# 4x4-programmable-keypad.net
KiCad netlist of a schematic drawn in EAGLE
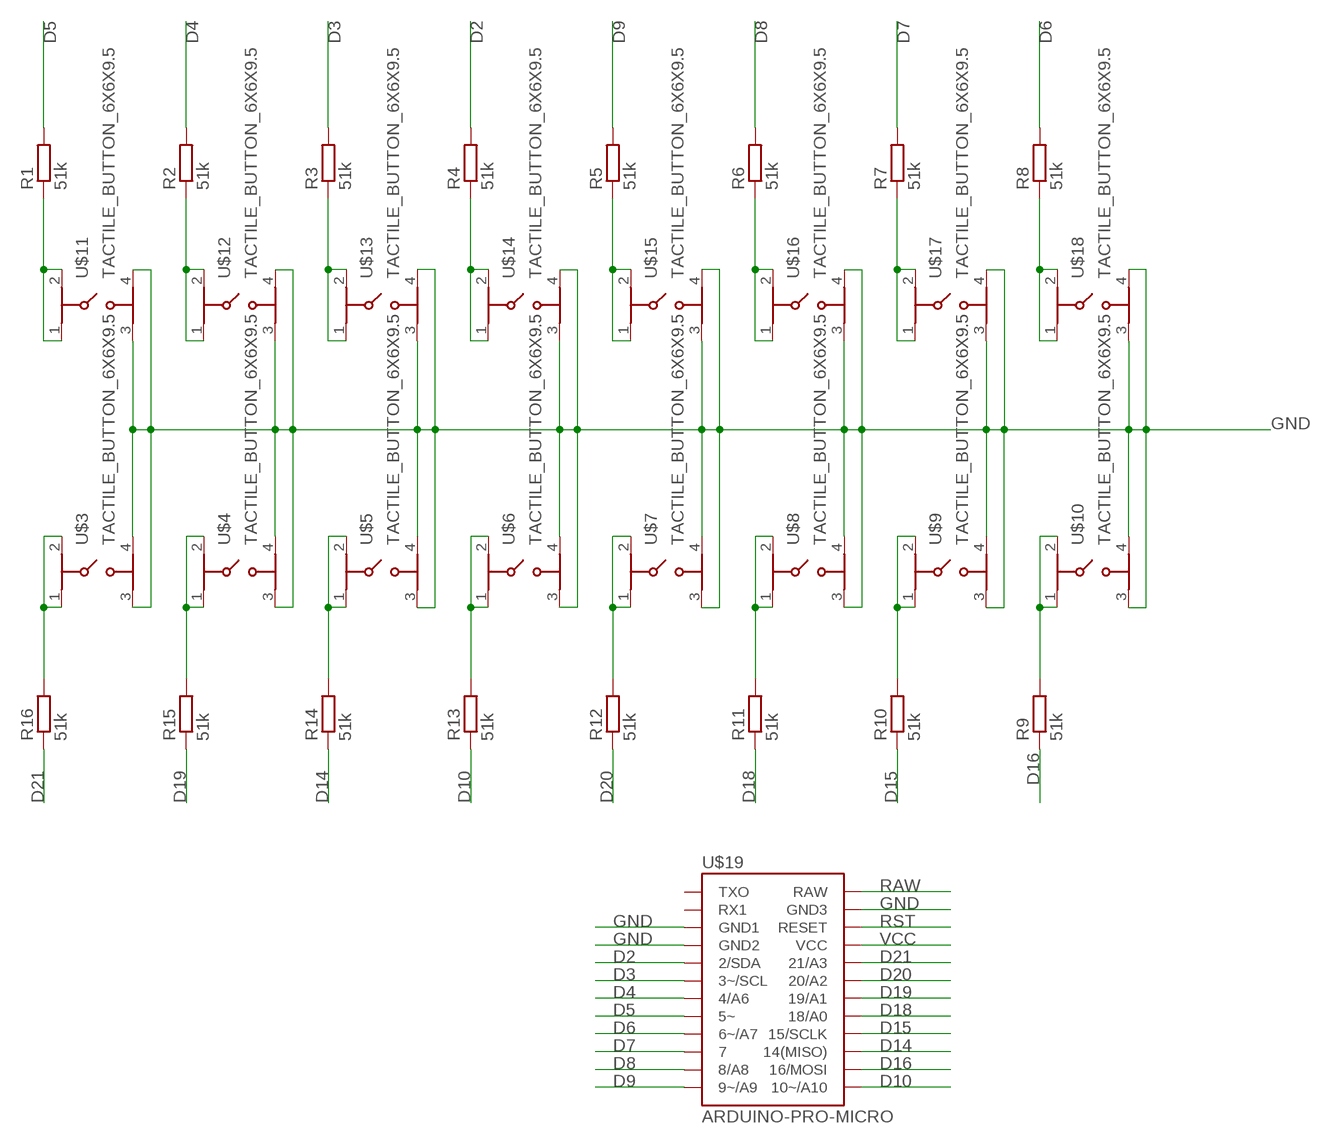
[diagram p0: schematic, sheet 1]

(export (version "E")
  (design (tool "Eeschema 10.0.6"))
  (components
    (comp (ref "R1")
      (value "51k")
      (footprint "eagle-import:R0603")
      (libsource (lib "eagle-import") (part "R-EU_R0603"))
    )
    (comp (ref "R2")
      (value "51k")
      (footprint "eagle-import:R0603")
      (libsource (lib "eagle-import") (part "R-EU_R0603"))
    )
    (comp (ref "R3")
      (value "51k")
      (footprint "eagle-import:R0603")
      (libsource (lib "eagle-import") (part "R-EU_R0603"))
    )
    (comp (ref "R4")
      (value "51k")
      (footprint "eagle-import:R0603")
      (libsource (lib "eagle-import") (part "R-EU_R0603"))
    )
    (comp (ref "R5")
      (value "51k")
      (footprint "eagle-import:R0603")
      (libsource (lib "eagle-import") (part "R-EU_R0603"))
    )
    (comp (ref "R6")
      (value "51k")
      (footprint "eagle-import:R0603")
      (libsource (lib "eagle-import") (part "R-EU_R0603"))
    )
    (comp (ref "R7")
      (value "51k")
      (footprint "eagle-import:R0603")
      (libsource (lib "eagle-import") (part "R-EU_R0603"))
    )
    (comp (ref "R8")
      (value "51k")
      (footprint "eagle-import:R0603")
      (libsource (lib "eagle-import") (part "R-EU_R0603"))
    )
    (comp (ref "R9")
      (value "51k")
      (footprint "eagle-import:R0603")
      (libsource (lib "eagle-import") (part "R-EU_R0603"))
    )
    (comp (ref "R10")
      (value "51k")
      (footprint "eagle-import:R0603")
      (libsource (lib "eagle-import") (part "R-EU_R0603"))
    )
    (comp (ref "R11")
      (value "51k")
      (footprint "eagle-import:R0603")
      (libsource (lib "eagle-import") (part "R-EU_R0603"))
    )
    (comp (ref "R12")
      (value "51k")
      (footprint "eagle-import:R0603")
      (libsource (lib "eagle-import") (part "R-EU_R0603"))
    )
    (comp (ref "R13")
      (value "51k")
      (footprint "eagle-import:R0603")
      (libsource (lib "eagle-import") (part "R-EU_R0603"))
    )
    (comp (ref "R14")
      (value "51k")
      (footprint "eagle-import:R0603")
      (libsource (lib "eagle-import") (part "R-EU_R0603"))
    )
    (comp (ref "R15")
      (value "51k")
      (footprint "eagle-import:R0603")
      (libsource (lib "eagle-import") (part "R-EU_R0603"))
    )
    (comp (ref "R16")
      (value "51k")
      (footprint "eagle-import:R0603")
      (libsource (lib "eagle-import") (part "R-EU_R0603"))
    )
    (comp (ref "U$3")
      (value "TACTILE_BUTTON_6X6X9.5")
      (footprint "eagle-import:TACTILE_SWITCH_PTH_6.0MM")
      (libsource (lib "eagle-import") (part "TACTILE_BUTTON_6X6X9.5"))
    )
    (comp (ref "U$4")
      (value "TACTILE_BUTTON_6X6X9.5")
      (footprint "eagle-import:TACTILE_SWITCH_PTH_6.0MM")
      (libsource (lib "eagle-import") (part "TACTILE_BUTTON_6X6X9.5"))
    )
    (comp (ref "U$5")
      (value "TACTILE_BUTTON_6X6X9.5")
      (footprint "eagle-import:TACTILE_SWITCH_PTH_6.0MM")
      (libsource (lib "eagle-import") (part "TACTILE_BUTTON_6X6X9.5"))
    )
    (comp (ref "U$6")
      (value "TACTILE_BUTTON_6X6X9.5")
      (footprint "eagle-import:TACTILE_SWITCH_PTH_6.0MM")
      (libsource (lib "eagle-import") (part "TACTILE_BUTTON_6X6X9.5"))
    )
    (comp (ref "U$7")
      (value "TACTILE_BUTTON_6X6X9.5")
      (footprint "eagle-import:TACTILE_SWITCH_PTH_6.0MM")
      (libsource (lib "eagle-import") (part "TACTILE_BUTTON_6X6X9.5"))
    )
    (comp (ref "U$8")
      (value "TACTILE_BUTTON_6X6X9.5")
      (footprint "eagle-import:TACTILE_SWITCH_PTH_6.0MM")
      (libsource (lib "eagle-import") (part "TACTILE_BUTTON_6X6X9.5"))
    )
    (comp (ref "U$9")
      (value "TACTILE_BUTTON_6X6X9.5")
      (footprint "eagle-import:TACTILE_SWITCH_PTH_6.0MM")
      (libsource (lib "eagle-import") (part "TACTILE_BUTTON_6X6X9.5"))
    )
    (comp (ref "U$10")
      (value "TACTILE_BUTTON_6X6X9.5")
      (footprint "eagle-import:TACTILE_SWITCH_PTH_6.0MM")
      (libsource (lib "eagle-import") (part "TACTILE_BUTTON_6X6X9.5"))
    )
    (comp (ref "U$11")
      (value "TACTILE_BUTTON_6X6X9.5")
      (footprint "eagle-import:TACTILE_SWITCH_PTH_6.0MM")
      (libsource (lib "eagle-import") (part "TACTILE_BUTTON_6X6X9.5"))
    )
    (comp (ref "U$12")
      (value "TACTILE_BUTTON_6X6X9.5")
      (footprint "eagle-import:TACTILE_SWITCH_PTH_6.0MM")
      (libsource (lib "eagle-import") (part "TACTILE_BUTTON_6X6X9.5"))
    )
    (comp (ref "U$13")
      (value "TACTILE_BUTTON_6X6X9.5")
      (footprint "eagle-import:TACTILE_SWITCH_PTH_6.0MM")
      (libsource (lib "eagle-import") (part "TACTILE_BUTTON_6X6X9.5"))
    )
    (comp (ref "U$14")
      (value "TACTILE_BUTTON_6X6X9.5")
      (footprint "eagle-import:TACTILE_SWITCH_PTH_6.0MM")
      (libsource (lib "eagle-import") (part "TACTILE_BUTTON_6X6X9.5"))
    )
    (comp (ref "U$15")
      (value "TACTILE_BUTTON_6X6X9.5")
      (footprint "eagle-import:TACTILE_SWITCH_PTH_6.0MM")
      (libsource (lib "eagle-import") (part "TACTILE_BUTTON_6X6X9.5"))
    )
    (comp (ref "U$16")
      (value "TACTILE_BUTTON_6X6X9.5")
      (footprint "eagle-import:TACTILE_SWITCH_PTH_6.0MM")
      (libsource (lib "eagle-import") (part "TACTILE_BUTTON_6X6X9.5"))
    )
    (comp (ref "U$17")
      (value "TACTILE_BUTTON_6X6X9.5")
      (footprint "eagle-import:TACTILE_SWITCH_PTH_6.0MM")
      (libsource (lib "eagle-import") (part "TACTILE_BUTTON_6X6X9.5"))
    )
    (comp (ref "U$18")
      (value "TACTILE_BUTTON_6X6X9.5")
      (footprint "eagle-import:TACTILE_SWITCH_PTH_6.0MM")
      (libsource (lib "eagle-import") (part "TACTILE_BUTTON_6X6X9.5"))
    )
    (comp (ref "U$19")
      (value "ARDUINO-PRO-MICRO")
      (footprint "eagle-import:SPARKFUN_PRO_MICRO")
      (libsource (lib "eagle-import") (part "ARDUINO-PRO-MICRO"))
    )
  )
  (nets
    (net (code "1") (name "/D2") (class "Default")
      (node (ref "R4") (pin "2") (pinfunction "2_2") (pintype "passive"))
      (node (ref "U$19") (pin "2/SDA") (pinfunction "2/SDA_2/SDA") (pintype "bidirectional"))
    )
    (net (code "2") (name "/D3") (class "Default")
      (node (ref "R3") (pin "2") (pinfunction "2_2") (pintype "passive"))
      (node (ref "U$19") (pin "3~/SCL") (pinfunction "3~{/SCL}_3~/SCL") (pintype "bidirectional"))
    )
    (net (code "3") (name "/D4") (class "Default")
      (node (ref "R2") (pin "2") (pinfunction "2_2") (pintype "passive"))
      (node (ref "U$19") (pin "4/A6") (pinfunction "4/A6_4/A6") (pintype "bidirectional"))
    )
    (net (code "4") (name "/D5") (class "Default")
      (node (ref "R1") (pin "2") (pinfunction "2_2") (pintype "passive"))
      (node (ref "U$19") (pin "5~") (pinfunction "5~{}_5~") (pintype "bidirectional"))
    )
    (net (code "5") (name "/D6") (class "Default")
      (node (ref "R8") (pin "2") (pinfunction "2_2") (pintype "passive"))
      (node (ref "U$19") (pin "6~/A7") (pinfunction "6~{/A7}_6~/A7") (pintype "bidirectional"))
    )
    (net (code "6") (name "/D7") (class "Default")
      (node (ref "R7") (pin "2") (pinfunction "2_2") (pintype "passive"))
      (node (ref "U$19") (pin "7") (pinfunction "7_7") (pintype "bidirectional"))
    )
    (net (code "7") (name "/D8") (class "Default")
      (node (ref "R6") (pin "2") (pinfunction "2_2") (pintype "passive"))
      (node (ref "U$19") (pin "8/A8") (pinfunction "8/A8_8/A8") (pintype "bidirectional"))
    )
    (net (code "8") (name "/D9") (class "Default")
      (node (ref "R5") (pin "2") (pinfunction "2_2") (pintype "passive"))
      (node (ref "U$19") (pin "9~/A9") (pinfunction "9~{/A9}_9~/A9") (pintype "bidirectional"))
    )
    (net (code "9") (name "/D10") (class "Default")
      (node (ref "R13") (pin "1") (pinfunction "1_1") (pintype "passive"))
      (node (ref "U$19") (pin "10~/A10") (pinfunction "10~{/A10}_10~/A10") (pintype "bidirectional"))
    )
    (net (code "10") (name "/D14") (class "Default")
      (node (ref "R14") (pin "1") (pinfunction "1_1") (pintype "passive"))
      (node (ref "U$19") (pin "14/MISO") (pinfunction "14(MISO)_14/MISO") (pintype "bidirectional"))
    )
    (net (code "11") (name "/D15") (class "Default")
      (node (ref "R10") (pin "1") (pinfunction "1_1") (pintype "passive"))
      (node (ref "U$19") (pin "15/SCLK") (pinfunction "15/SCLK_15/SCLK") (pintype "bidirectional"))
    )
    (net (code "12") (name "/D16") (class "Default")
      (node (ref "R9") (pin "1") (pinfunction "1_1") (pintype "passive"))
      (node (ref "U$19") (pin "16/MOSI") (pinfunction "16/MOSI_16/MOSI") (pintype "bidirectional"))
    )
    (net (code "13") (name "/D18") (class "Default")
      (node (ref "R11") (pin "1") (pinfunction "1_1") (pintype "passive"))
      (node (ref "U$19") (pin "18/A0") (pinfunction "18/A0_18/A0") (pintype "bidirectional"))
    )
    (net (code "14") (name "/D19") (class "Default")
      (node (ref "R15") (pin "1") (pinfunction "1_1") (pintype "passive"))
      (node (ref "U$19") (pin "19/A1") (pinfunction "19/A1_19/A1") (pintype "bidirectional"))
    )
    (net (code "15") (name "/D20") (class "Default")
      (node (ref "R12") (pin "1") (pinfunction "1_1") (pintype "passive"))
      (node (ref "U$19") (pin "20/A2") (pinfunction "20/A2_20/A2") (pintype "bidirectional"))
    )
    (net (code "16") (name "/D21") (class "Default")
      (node (ref "R16") (pin "1") (pinfunction "1_1") (pintype "passive"))
      (node (ref "U$19") (pin "21/A3") (pinfunction "21/A3_21/A3") (pintype "bidirectional"))
    )
    (net (code "17") (name "/GND") (class "Default")
      (node (ref "U$10") (pin "3") (pinfunction "2_3") (pintype "passive"))
      (node (ref "U$10") (pin "4") (pinfunction "4_4") (pintype "passive"))
      (node (ref "U$11") (pin "3") (pinfunction "2_3") (pintype "passive"))
      (node (ref "U$11") (pin "4") (pinfunction "4_4") (pintype "passive"))
      (node (ref "U$12") (pin "3") (pinfunction "2_3") (pintype "passive"))
      (node (ref "U$12") (pin "4") (pinfunction "4_4") (pintype "passive"))
      (node (ref "U$13") (pin "3") (pinfunction "2_3") (pintype "passive"))
      (node (ref "U$13") (pin "4") (pinfunction "4_4") (pintype "passive"))
      (node (ref "U$14") (pin "3") (pinfunction "2_3") (pintype "passive"))
      (node (ref "U$14") (pin "4") (pinfunction "4_4") (pintype "passive"))
      (node (ref "U$15") (pin "3") (pinfunction "2_3") (pintype "passive"))
      (node (ref "U$15") (pin "4") (pinfunction "4_4") (pintype "passive"))
      (node (ref "U$16") (pin "3") (pinfunction "2_3") (pintype "passive"))
      (node (ref "U$16") (pin "4") (pinfunction "4_4") (pintype "passive"))
      (node (ref "U$17") (pin "3") (pinfunction "2_3") (pintype "passive"))
      (node (ref "U$17") (pin "4") (pinfunction "4_4") (pintype "passive"))
      (node (ref "U$18") (pin "3") (pinfunction "2_3") (pintype "passive"))
      (node (ref "U$18") (pin "4") (pinfunction "4_4") (pintype "passive"))
      (node (ref "U$19") (pin "GND1") (pinfunction "GND1_GND1") (pintype "power_in"))
      (node (ref "U$19") (pin "GND2") (pinfunction "GND2_GND2") (pintype "power_in"))
      (node (ref "U$19") (pin "GND3") (pinfunction "GND3_GND3") (pintype "power_in"))
      (node (ref "U$3") (pin "3") (pinfunction "2_3") (pintype "passive"))
      (node (ref "U$3") (pin "4") (pinfunction "4_4") (pintype "passive"))
      (node (ref "U$4") (pin "3") (pinfunction "2_3") (pintype "passive"))
      (node (ref "U$4") (pin "4") (pinfunction "4_4") (pintype "passive"))
      (node (ref "U$5") (pin "3") (pinfunction "2_3") (pintype "passive"))
      (node (ref "U$5") (pin "4") (pinfunction "4_4") (pintype "passive"))
      (node (ref "U$6") (pin "3") (pinfunction "2_3") (pintype "passive"))
      (node (ref "U$6") (pin "4") (pinfunction "4_4") (pintype "passive"))
      (node (ref "U$7") (pin "3") (pinfunction "2_3") (pintype "passive"))
      (node (ref "U$7") (pin "4") (pinfunction "4_4") (pintype "passive"))
      (node (ref "U$8") (pin "3") (pinfunction "2_3") (pintype "passive"))
      (node (ref "U$8") (pin "4") (pinfunction "4_4") (pintype "passive"))
      (node (ref "U$9") (pin "3") (pinfunction "2_3") (pintype "passive"))
      (node (ref "U$9") (pin "4") (pinfunction "4_4") (pintype "passive"))
    )
    (net (code "18") (name "/RAW") (class "Default")
      (node (ref "U$19") (pin "RAW") (pinfunction "RAW_RAW") (pintype "power_in"))
    )
    (net (code "19") (name "/RST") (class "Default")
      (node (ref "U$19") (pin "RST") (pinfunction "RESET_RST") (pintype "bidirectional"))
    )
    (net (code "20") (name "/VCC") (class "Default")
      (node (ref "U$19") (pin "VCC") (pinfunction "VCC_VCC") (pintype "power_in"))
    )
    (net (code "21") (name "Net-(U$3-3)") (class "Default")
      (node (ref "R16") (pin "2") (pinfunction "2_2") (pintype "passive"))
      (node (ref "U$3") (pin "1") (pinfunction "1_1") (pintype "passive"))
      (node (ref "U$3") (pin "2") (pinfunction "3_2") (pintype "passive"))
    )
    (net (code "22") (name "Net-(U$4-3)") (class "Default")
      (node (ref "R15") (pin "2") (pinfunction "2_2") (pintype "passive"))
      (node (ref "U$4") (pin "1") (pinfunction "1_1") (pintype "passive"))
      (node (ref "U$4") (pin "2") (pinfunction "3_2") (pintype "passive"))
    )
    (net (code "23") (name "Net-(U$5-3)") (class "Default")
      (node (ref "R14") (pin "2") (pinfunction "2_2") (pintype "passive"))
      (node (ref "U$5") (pin "1") (pinfunction "1_1") (pintype "passive"))
      (node (ref "U$5") (pin "2") (pinfunction "3_2") (pintype "passive"))
    )
    (net (code "24") (name "Net-(U$6-3)") (class "Default")
      (node (ref "R13") (pin "2") (pinfunction "2_2") (pintype "passive"))
      (node (ref "U$6") (pin "1") (pinfunction "1_1") (pintype "passive"))
      (node (ref "U$6") (pin "2") (pinfunction "3_2") (pintype "passive"))
    )
    (net (code "25") (name "Net-(U$7-3)") (class "Default")
      (node (ref "R12") (pin "2") (pinfunction "2_2") (pintype "passive"))
      (node (ref "U$7") (pin "1") (pinfunction "1_1") (pintype "passive"))
      (node (ref "U$7") (pin "2") (pinfunction "3_2") (pintype "passive"))
    )
    (net (code "26") (name "Net-(U$8-3)") (class "Default")
      (node (ref "R11") (pin "2") (pinfunction "2_2") (pintype "passive"))
      (node (ref "U$8") (pin "1") (pinfunction "1_1") (pintype "passive"))
      (node (ref "U$8") (pin "2") (pinfunction "3_2") (pintype "passive"))
    )
    (net (code "27") (name "Net-(U$9-3)") (class "Default")
      (node (ref "R10") (pin "2") (pinfunction "2_2") (pintype "passive"))
      (node (ref "U$9") (pin "1") (pinfunction "1_1") (pintype "passive"))
      (node (ref "U$9") (pin "2") (pinfunction "3_2") (pintype "passive"))
    )
    (net (code "28") (name "Net-(U$10-3)") (class "Default")
      (node (ref "R9") (pin "2") (pinfunction "2_2") (pintype "passive"))
      (node (ref "U$10") (pin "1") (pinfunction "1_1") (pintype "passive"))
      (node (ref "U$10") (pin "2") (pinfunction "3_2") (pintype "passive"))
    )
    (net (code "29") (name "Net-(U$11-3)") (class "Default")
      (node (ref "R1") (pin "1") (pinfunction "1_1") (pintype "passive"))
      (node (ref "U$11") (pin "1") (pinfunction "1_1") (pintype "passive"))
      (node (ref "U$11") (pin "2") (pinfunction "3_2") (pintype "passive"))
    )
    (net (code "30") (name "Net-(U$12-3)") (class "Default")
      (node (ref "R2") (pin "1") (pinfunction "1_1") (pintype "passive"))
      (node (ref "U$12") (pin "1") (pinfunction "1_1") (pintype "passive"))
      (node (ref "U$12") (pin "2") (pinfunction "3_2") (pintype "passive"))
    )
    (net (code "31") (name "Net-(U$13-3)") (class "Default")
      (node (ref "R3") (pin "1") (pinfunction "1_1") (pintype "passive"))
      (node (ref "U$13") (pin "1") (pinfunction "1_1") (pintype "passive"))
      (node (ref "U$13") (pin "2") (pinfunction "3_2") (pintype "passive"))
    )
    (net (code "32") (name "Net-(U$14-3)") (class "Default")
      (node (ref "R4") (pin "1") (pinfunction "1_1") (pintype "passive"))
      (node (ref "U$14") (pin "1") (pinfunction "1_1") (pintype "passive"))
      (node (ref "U$14") (pin "2") (pinfunction "3_2") (pintype "passive"))
    )
    (net (code "33") (name "Net-(U$15-3)") (class "Default")
      (node (ref "R5") (pin "1") (pinfunction "1_1") (pintype "passive"))
      (node (ref "U$15") (pin "1") (pinfunction "1_1") (pintype "passive"))
      (node (ref "U$15") (pin "2") (pinfunction "3_2") (pintype "passive"))
    )
    (net (code "34") (name "Net-(U$16-3)") (class "Default")
      (node (ref "R6") (pin "1") (pinfunction "1_1") (pintype "passive"))
      (node (ref "U$16") (pin "1") (pinfunction "1_1") (pintype "passive"))
      (node (ref "U$16") (pin "2") (pinfunction "3_2") (pintype "passive"))
    )
    (net (code "35") (name "Net-(U$17-3)") (class "Default")
      (node (ref "R7") (pin "1") (pinfunction "1_1") (pintype "passive"))
      (node (ref "U$17") (pin "1") (pinfunction "1_1") (pintype "passive"))
      (node (ref "U$17") (pin "2") (pinfunction "3_2") (pintype "passive"))
    )
    (net (code "36") (name "Net-(U$18-3)") (class "Default")
      (node (ref "R8") (pin "1") (pinfunction "1_1") (pintype "passive"))
      (node (ref "U$18") (pin "1") (pinfunction "1_1") (pintype "passive"))
      (node (ref "U$18") (pin "2") (pinfunction "3_2") (pintype "passive"))
    )
    (net (code "37") (name "unconnected-(U$19-PadRX1)") (class "Default")
      (node (ref "U$19") (pin "RX1") (pinfunction "RX1_RX1") (pintype "bidirectional"))
    )
    (net (code "38") (name "unconnected-(U$19-TXO-PadTX0)") (class "Default")
      (node (ref "U$19") (pin "TX0") (pinfunction "TXO_TX0") (pintype "bidirectional"))
    )
  )
)
